# ad5272_arduino_ethernet.net
KiCad netlist of a schematic drawn in EAGLE
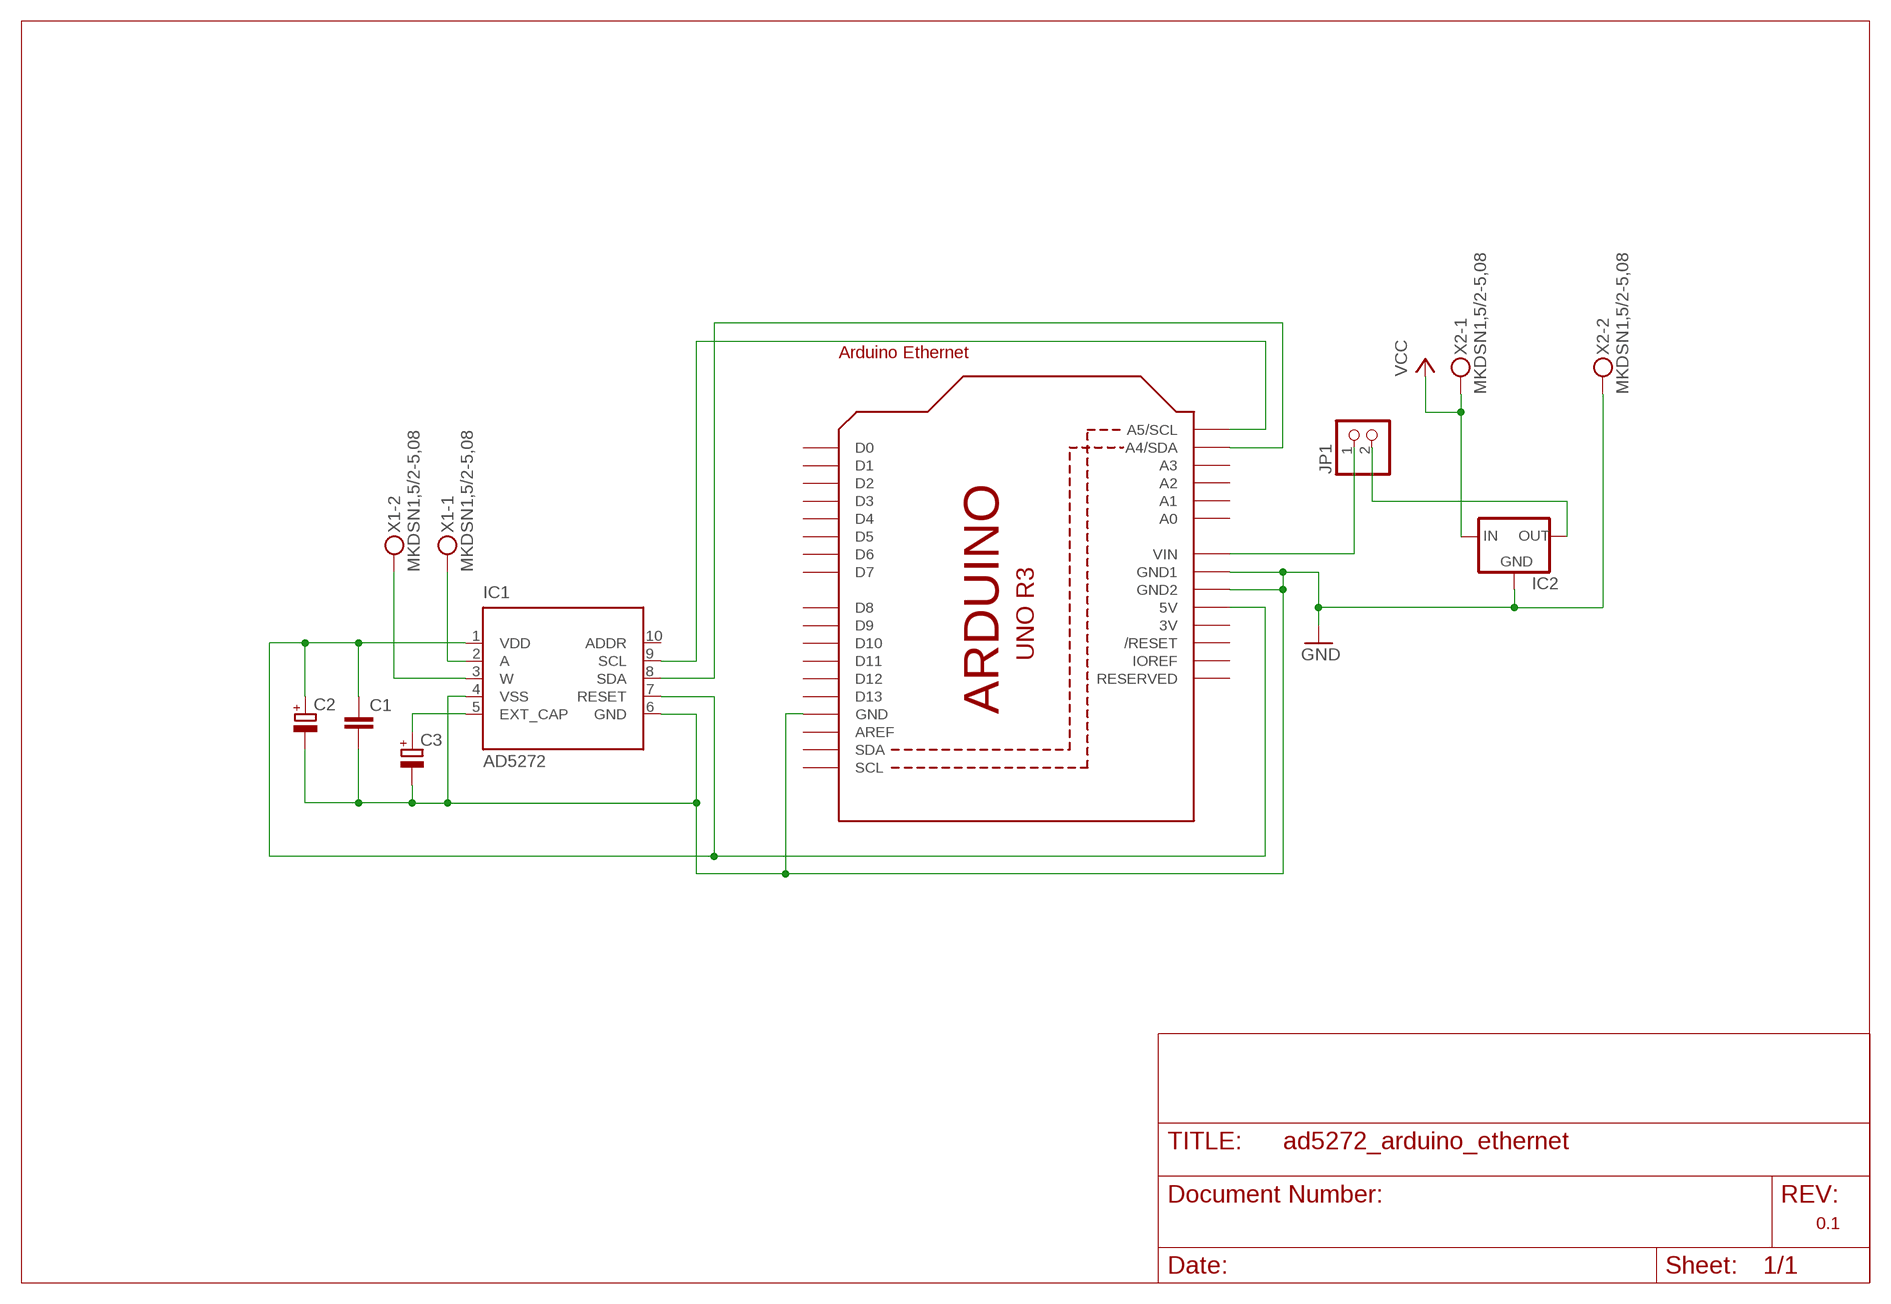
[diagram p0: schematic, sheet 1]

(export (version "E")
  (design (tool "Eeschema 10.0.6"))
  (components
    (comp (ref "C1")
      (value "C-EU050-024X044")
      (footprint "eagle-import:C050-024X044")
      (libsource (lib "eagle-import") (part "C-EU050-024X044"))
    )
    (comp (ref "C2")
      (value "CPOL-EUE2.5-7")
      (footprint "eagle-import:E2,5-7")
      (libsource (lib "eagle-import") (part "CPOL-EUE2.5-7"))
    )
    (comp (ref "C3")
      (value "CPOL-EUE2.5-7")
      (footprint "eagle-import:E2,5-7")
      (libsource (lib "eagle-import") (part "CPOL-EUE2.5-7"))
    )
    (comp (ref "IC1")
      (value "AD5272")
      (footprint "eagle-import:MSOP10")
      (fields (field (name "MPN") "AD7992BRMZ-0"))
      (libsource (lib "eagle-import") (part "AD5272"))
    )
    (comp (ref "IC2")
      (value "78XXL")
      (footprint "eagle-import:78XXL")
      (libsource (lib "eagle-import") (part "78XXL"))
    )
    (comp (ref "JP1")
      (value "PINHD-1X2")
      (footprint "eagle-import:1X02")
      (libsource (lib "eagle-import") (part "PINHD-1X2"))
    )
    (comp (ref "U1")
      (value "ARDUINOR3-DIMENSION")
      (footprint "eagle-import:ARDUINOR3")
      (libsource (lib "eagle-import") (part "ARDUINOR3-DIMENSION"))
    )
    (comp (ref "X1")
      (value "MKDSN1,5/2-5,08")
      (footprint "eagle-import:MKDSN1,5_2-5,08")
      (fields (field (name "MPN") "MKDSN 1,5/2-5.08"))
      (libsource (lib "eagle-import") (part "MKDSN1,5/2-5,08"))
    )
    (comp (ref "X2")
      (value "MKDSN1,5/2-5,08")
      (footprint "eagle-import:MKDSN1,5_2-5,08")
      (fields (field (name "MPN") "MKDSN 1,5/2-5.08"))
      (libsource (lib "eagle-import") (part "MKDSN1,5/2-5,08"))
    )
  )
  (nets
    (net (code "1") (name "/3V") (class "Default")
      (node (ref "U1") (pin "3V") (pinfunction "3V_3V") (pintype "power_in"))
    )
    (net (code "2") (name "GND") (class "Default")
      (node (ref "C1") (pin "2") (pinfunction "2_2") (pintype "passive"))
      (node (ref "C2") (pin "-") (pinfunction "-_-") (pintype "passive"))
      (node (ref "C3") (pin "-") (pinfunction "-_-") (pintype "passive"))
      (node (ref "IC1") (pin "4") (pinfunction "VSS_4") (pintype "power_in"))
      (node (ref "IC1") (pin "6") (pinfunction "GND_6") (pintype "power_in"))
      (node (ref "IC2") (pin "GND") (pinfunction "GND_GND") (pintype "input"))
      (node (ref "U1") (pin "GND") (pinfunction "GND_GND") (pintype "power_in"))
      (node (ref "U1") (pin "GND1") (pinfunction "GND1_GND1") (pintype "power_in"))
      (node (ref "U1") (pin "GND2") (pinfunction "GND2_GND2") (pintype "power_in"))
      (node (ref "X2") (pin "2") (pinfunction "KL_2") (pintype "passive"))
    )
    (net (code "3") (name "Net-(IC1-A)") (class "Default")
      (node (ref "IC1") (pin "2") (pinfunction "A_2") (pintype "bidirectional"))
      (node (ref "X1") (pin "1") (pinfunction "KL_1") (pintype "passive"))
    )
    (net (code "4") (name "Net-(IC1-EXT_CAP)") (class "Default")
      (node (ref "C3") (pin "+") (pinfunction "+_+") (pintype "passive"))
      (node (ref "IC1") (pin "5") (pinfunction "EXT_CAP_5") (pintype "passive"))
    )
    (net (code "5") (name "Net-(IC1-RESET)") (class "Default")
      (node (ref "C1") (pin "1") (pinfunction "1_1") (pintype "passive"))
      (node (ref "C2") (pin "+") (pinfunction "+_+") (pintype "passive"))
      (node (ref "IC1") (pin "1") (pinfunction "VDD_1") (pintype "power_in"))
      (node (ref "IC1") (pin "7") (pinfunction "RESET_7") (pintype "input"))
      (node (ref "U1") (pin "5V") (pinfunction "5V_5V") (pintype "power_in"))
    )
    (net (code "6") (name "Net-(IC1-SCL)") (class "Default")
      (node (ref "IC1") (pin "9") (pinfunction "SCL_9") (pintype "output"))
      (node (ref "U1") (pin "A5") (pinfunction "A5/SCL_A5") (pintype "bidirectional"))
    )
    (net (code "7") (name "Net-(IC1-SDA)") (class "Default")
      (node (ref "IC1") (pin "8") (pinfunction "SDA_8") (pintype "bidirectional"))
      (node (ref "U1") (pin "A4") (pinfunction "A4/SDA_A4") (pintype "bidirectional"))
    )
    (net (code "8") (name "Net-(IC1-W)") (class "Default")
      (node (ref "IC1") (pin "3") (pinfunction "W_3") (pintype "bidirectional"))
      (node (ref "X1") (pin "2") (pinfunction "KL_2") (pintype "passive"))
    )
    (net (code "9") (name "Net-(IC2-PadOUT)") (class "Default")
      (node (ref "IC2") (pin "OUT") (pinfunction "OUT_OUT") (pintype "passive"))
      (node (ref "JP1") (pin "2") (pinfunction "2_2") (pintype "passive"))
    )
    (net (code "10") (name "Net-(JP1-Pad1)") (class "Default")
      (node (ref "JP1") (pin "1") (pinfunction "1_1") (pintype "passive"))
      (node (ref "U1") (pin "VIN") (pinfunction "VIN_VIN") (pintype "power_in"))
    )
    (net (code "11") (name "VCC") (class "Default")
      (node (ref "IC2") (pin "IN") (pinfunction "IN_IN") (pintype "input"))
      (node (ref "X2") (pin "1") (pinfunction "KL_1") (pintype "passive"))
    )
    (net (code "12") (name "unconnected-(IC1-ADDR-Pad10)") (class "Default")
      (node (ref "IC1") (pin "10") (pinfunction "ADDR_10") (pintype "input"))
    )
    (net (code "13") (name "unconnected-(U1-PadA0)") (class "Default")
      (node (ref "U1") (pin "A0") (pinfunction "A0_A0") (pintype "bidirectional"))
    )
    (net (code "14") (name "unconnected-(U1-PadA1)") (class "Default")
      (node (ref "U1") (pin "A1") (pinfunction "A1_A1") (pintype "bidirectional"))
    )
    (net (code "15") (name "unconnected-(U1-PadA2)") (class "Default")
      (node (ref "U1") (pin "A2") (pinfunction "A2_A2") (pintype "bidirectional"))
    )
    (net (code "16") (name "unconnected-(U1-PadA3)") (class "Default")
      (node (ref "U1") (pin "A3") (pinfunction "A3_A3") (pintype "bidirectional"))
    )
    (net (code "17") (name "unconnected-(U1-PadAREF)") (class "Default")
      (node (ref "U1") (pin "AREF") (pinfunction "AREF_AREF") (pintype "bidirectional"))
    )
    (net (code "18") (name "unconnected-(U1-PadD0)") (class "Default")
      (node (ref "U1") (pin "D0") (pinfunction "D0_D0") (pintype "bidirectional"))
    )
    (net (code "19") (name "unconnected-(U1-PadD1)") (class "Default")
      (node (ref "U1") (pin "D1") (pinfunction "D1_D1") (pintype "bidirectional"))
    )
    (net (code "20") (name "unconnected-(U1-PadD2)") (class "Default")
      (node (ref "U1") (pin "D2") (pinfunction "D2_D2") (pintype "bidirectional"))
    )
    (net (code "21") (name "unconnected-(U1-PadD3)") (class "Default")
      (node (ref "U1") (pin "D3") (pinfunction "D3_D3") (pintype "bidirectional"))
    )
    (net (code "22") (name "unconnected-(U1-PadD4)") (class "Default")
      (node (ref "U1") (pin "D4") (pinfunction "D4_D4") (pintype "bidirectional"))
    )
    (net (code "23") (name "unconnected-(U1-PadD5)") (class "Default")
      (node (ref "U1") (pin "D5") (pinfunction "D5_D5") (pintype "bidirectional"))
    )
    (net (code "24") (name "unconnected-(U1-PadD6)") (class "Default")
      (node (ref "U1") (pin "D6") (pinfunction "D6_D6") (pintype "bidirectional"))
    )
    (net (code "25") (name "unconnected-(U1-PadD7)") (class "Default")
      (node (ref "U1") (pin "D7") (pinfunction "D7_D7") (pintype "bidirectional"))
    )
    (net (code "26") (name "unconnected-(U1-PadD8)") (class "Default")
      (node (ref "U1") (pin "D8") (pinfunction "D8_D8") (pintype "bidirectional"))
    )
    (net (code "27") (name "unconnected-(U1-PadD9)") (class "Default")
      (node (ref "U1") (pin "D9") (pinfunction "D9_D9") (pintype "bidirectional"))
    )
    (net (code "28") (name "unconnected-(U1-PadD10)") (class "Default")
      (node (ref "U1") (pin "D10") (pinfunction "D10_D10") (pintype "bidirectional"))
    )
    (net (code "29") (name "unconnected-(U1-PadD11)") (class "Default")
      (node (ref "U1") (pin "D11") (pinfunction "D11_D11") (pintype "bidirectional"))
    )
    (net (code "30") (name "unconnected-(U1-PadD12)") (class "Default")
      (node (ref "U1") (pin "D12") (pinfunction "D12_D12") (pintype "bidirectional"))
    )
    (net (code "31") (name "unconnected-(U1-PadD13)") (class "Default")
      (node (ref "U1") (pin "D13") (pinfunction "D13_D13") (pintype "bidirectional"))
    )
    (net (code "32") (name "unconnected-(U1-PadIOREF)") (class "Default")
      (node (ref "U1") (pin "IOREF") (pinfunction "IOREF_IOREF") (pintype "output"))
    )
    (net (code "33") (name "unconnected-(U1-PadRESERVED)") (class "Default")
      (node (ref "U1") (pin "RESERVED") (pinfunction "RESERVED_RESERVED") (pintype "no_connect"))
    )
    (net (code "34") (name "unconnected-(U1-PadSCL)") (class "Default")
      (node (ref "U1") (pin "SCL") (pinfunction "SCL_SCL") (pintype "bidirectional"))
    )
    (net (code "35") (name "unconnected-(U1-PadSDA)") (class "Default")
      (node (ref "U1") (pin "SDA") (pinfunction "SDA_SDA") (pintype "bidirectional"))
    )
    (net (code "36") (name "unconnected-(U1-{slash}RESET-PadRESET)") (class "Default")
      (node (ref "U1") (pin "RESET") (pinfunction "/RESET_RESET") (pintype "bidirectional"))
    )
  )
)
